# Sheet_1_2020-09-11_10-02-54.net
KiCad netlist of a schematic drawn in Altium Designer
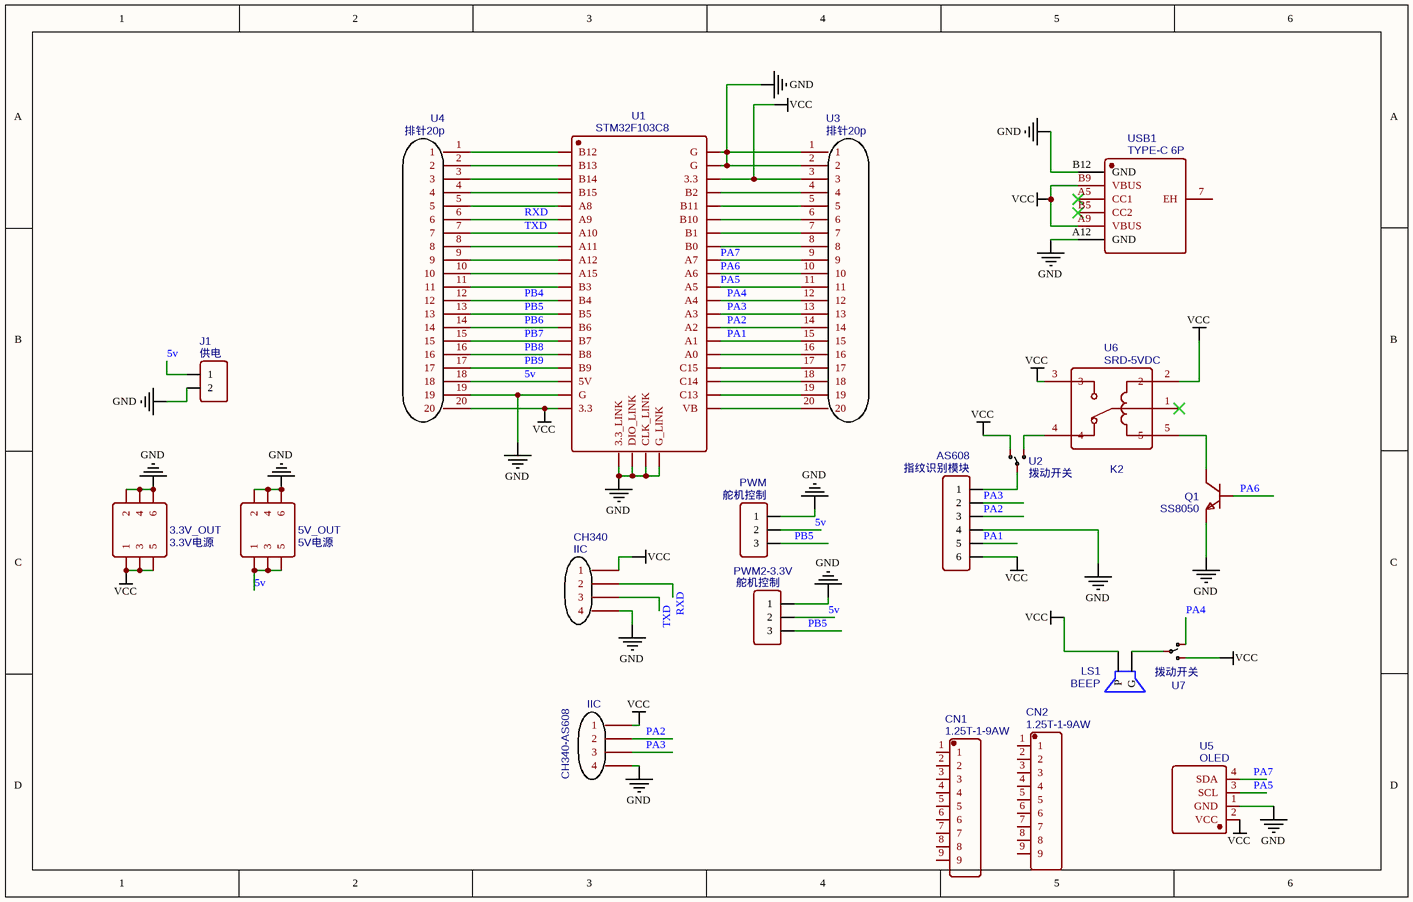
[diagram p0: Sheet_1_2020-09-11_10-02-54.schdoc]

(export (version "E")
  (design (tool "Eeschema 10.0.6"))
  (components
    (comp (ref "3.3V_OUT")
      (value "3.3V电源")
      (footprint "HDR-TH_6P-P2.54-V-R2-C3-S2.54")
      (fields
        (field (name "BOM_MANUFACTURER PART") "Header-Male-2.54_2x3")
        (field (name "BOM_SUPPLIER PART") "C65114")
      )
      (libsource (lib "altium-import") (part "root_1_3.3V电源_"))
    )
    (comp (ref "5V_OUT")
      (value "5V电源")
      (footprint "HDR-TH_6P-P2.54-V-R2-C3-S2.54")
      (fields
        (field (name "BOM_MANUFACTURER PART") "Header-Male-2.54_2x3")
        (field (name "BOM_SUPPLIER PART") "C65114")
      )
      (libsource (lib "altium-import") (part "root_1_5V电源_"))
    )
    (comp (ref "AS608")
      (value "指纹识别模块")
      (footprint "HDR-M-2.54_1X6")
      (fields (field (name "BOM_SUPPLIER PART") "C190819") (field (name "CONTRIBUTOR") "LCEDA_Lib"))
      (libsource (lib "altium-import") (part "root_0_指纹识别模块_"))
    )
    (comp (ref "CH340")
      (value "IIC")
      (footprint "HANDER*4")
      (fields (field (name "CONTRIBUTOR") "lzzzzzz"))
      (libsource (lib "altium-import") (part "root_0_IIC_"))
    )
    (comp (ref "CH340-AS608")
      (value "IIC")
      (footprint "HANDER*4")
      (fields (field (name "CONTRIBUTOR") "lzzzzzz"))
      (libsource (lib "altium-import") (part "root_0_IIC_"))
    )
    (comp (ref "CN1")
      (value "1.25T-1-9AW")
      (footprint "CONN-TH_9P-P1.25-H_1.25T-1-9AW")
      (fields (field (name "BOM_SUPPLIER PART") "C10839"))
      (libsource (lib "altium-import") (part "root_0_1.25T-1-9AW_"))
    )
    (comp (ref "CN2")
      (value "1.25T-1-9AW")
      (footprint "CONN-TH_9P-P1.25-H_1.25T-1-9AW")
      (fields (field (name "BOM_SUPPLIER PART") "C10839"))
      (libsource (lib "altium-import") (part "root_0_1.25T-1-9AW_"))
    )
    (comp (ref "J1")
      (value "供电")
      (footprint "HDR-M-2.54_1X2")
      (fields (field (name "BOM_SUPPLIER PART") "C124375") (field (name "CONTRIBUTOR") "LCEDA_Lib"))
      (libsource (lib "altium-import") (part "root_0_供电_"))
    )
    (comp (ref "LS1")
      (value "BEEP")
      (footprint "BEEP-9")
      (fields (field (name "CONTRIBUTOR") "nibo"))
      (libsource (lib "altium-import") (part "root_3_BEEP_"))
    )
    (comp (ref "PWM")
      (value "舵机控制")
      (footprint "HDR-M-2.54_1X3")
      (fields (field (name "BOM_SUPPLIER PART") "C180248") (field (name "CONTRIBUTOR") "LCEDA_Lib"))
      (libsource (lib "altium-import") (part "root_0_舵机控制_"))
    )
    (comp (ref "PWM2-3.3V")
      (value "舵机控制")
      (footprint "HDR-M-2.54_1X3")
      (fields (field (name "BOM_SUPPLIER PART") "C180248") (field (name "CONTRIBUTOR") "LCEDA_Lib"))
      (libsource (lib "altium-import") (part "root_0_舵机控制_"))
    )
    (comp (ref "Q1")
      (value "SS8050")
      (footprint "TO-92_FORMING1")
      (fields (field (name "BOM_SUPPLIER PART") "C80297"))
      (libsource (lib "altium-import") (part "root_0_SS8050_"))
    )
    (comp (ref "U1")
      (value "STM32F103C8")
      (footprint "STM32F103C8T6-CORE")
      (fields (field (name "CONTRIBUTOR") "TMHZ"))
      (libsource (lib "altium-import") (part "root_0_STM32F103C8_"))
    )
    (comp (ref "U2")
      (value "拨动开关")
      (footprint "拨动开关-SS12D00G3")
      (fields (field (name "CONTRIBUTOR") "ShiKerFamily"))
      (libsource (lib "altium-import") (part "root_2_拨动开关_"))
    )
    (comp (ref "U3")
      (value "排针20p")
      (footprint "排针-2.54间距-1*20P")
      (fields (field (name "CONTRIBUTOR") "liugj"))
      (libsource (lib "") (part "root_0_排针20p__1"))
    )
    (comp (ref "U4")
      (value "排针20p")
      (footprint "排针-2.54间距-1*20P")
      (fields (field (name "CONTRIBUTOR") "liugj"))
      (libsource (lib "altium-import") (part "root_0_排针20p_"))
    )
    (comp (ref "U5")
      (value "OLED")
      (footprint "0.96_OLED")
      (fields (field (name "CONTRIBUTOR") "Sheikah"))
      (libsource (lib "altium-import") (part "root_2_OLED_"))
    )
    (comp (ref "U6")
      (value "SRD-5VDC")
      (footprint "SRD-05VDC-SL-C")
      (fields (field (name "CONTRIBUTOR") "Jensen"))
      (libsource (lib "altium-import") (part "root_2_SRD-5VDC_"))
    )
    (comp (ref "U7")
      (value "拨动开关")
      (footprint "拨动开关-SS12D00G3")
      (fields (field (name "CONTRIBUTOR") "ShiKerFamily"))
      (libsource (lib "altium-import") (part "root_1_拨动开关_"))
    )
    (comp (ref "USB1")
      (value "TYPE-C 6P")
      (footprint "TYPE-C-SMD_TYPE-C-6P")
      (fields (field (name "BOM_SUPPLIER PART") "C456012") (field (name "CONTRIBUTOR") "youzige"))
      (libsource (lib "altium-import") (part "root_0_TYPE-C 6P_"))
    )
  )
  (nets
    (net (code "1") (name "/5v") (class "Default")
      (node (ref "5V_OUT") (pin "1") (pinfunction "1_1") (pintype "passive"))
      (node (ref "5V_OUT") (pin "3") (pinfunction "3_3") (pintype "passive"))
      (node (ref "5V_OUT") (pin "5") (pinfunction "5_5") (pintype "passive"))
      (node (ref "J1") (pin "1") (pinfunction "1_1") (pintype "passive"))
      (node (ref "PWM") (pin "2") (pinfunction "2_2") (pintype "passive"))
      (node (ref "PWM2-3.3V") (pin "2") (pinfunction "2_2") (pintype "passive"))
      (node (ref "U1") (pin "18") (pinfunction "5V_18") (pintype "passive"))
      (node (ref "U4") (pin "18") (pinfunction "18_18") (pintype "passive"))
    )
    (net (code "2") (name "/PA1") (class "Default")
      (node (ref "AS608") (pin "5") (pinfunction "5_5") (pintype "passive"))
      (node (ref "U1") (pin "26") (pinfunction "A1_26") (pintype "passive"))
      (node (ref "U3") (pin "15") (pinfunction "15_15") (pintype "passive"))
    )
    (net (code "3") (name "/PA2") (class "Default")
      (node (ref "AS608") (pin "3") (pinfunction "3_3") (pintype "passive"))
      (node (ref "CH340-AS608") (pin "2") (pinfunction "2_2") (pintype "passive"))
      (node (ref "U1") (pin "27") (pinfunction "A2_27") (pintype "passive"))
      (node (ref "U3") (pin "14") (pinfunction "14_14") (pintype "passive"))
    )
    (net (code "4") (name "/PA3") (class "Default")
      (node (ref "AS608") (pin "2") (pinfunction "2_2") (pintype "passive"))
      (node (ref "CH340-AS608") (pin "3") (pinfunction "3_3") (pintype "passive"))
      (node (ref "U1") (pin "28") (pinfunction "A3_28") (pintype "passive"))
      (node (ref "U3") (pin "13") (pinfunction "13_13") (pintype "passive"))
    )
    (net (code "5") (name "/PA4") (class "Default")
      (node (ref "U1") (pin "29") (pinfunction "A4_29") (pintype "passive"))
      (node (ref "U3") (pin "12") (pinfunction "12_12") (pintype "passive"))
      (node (ref "U7") (pin "3") (pinfunction "3_3") (pintype "passive"))
    )
    (net (code "6") (name "/PA5") (class "Default")
      (node (ref "U1") (pin "30") (pinfunction "A5_30") (pintype "passive"))
      (node (ref "U3") (pin "11") (pinfunction "11_11") (pintype "passive"))
      (node (ref "U5") (pin "3") (pinfunction "SCL_3") (pintype "passive"))
    )
    (net (code "7") (name "/PA6") (class "Default")
      (node (ref "Q1") (pin "2") (pinfunction "B_2") (pintype "passive"))
      (node (ref "U1") (pin "31") (pinfunction "A6_31") (pintype "passive"))
      (node (ref "U3") (pin "10") (pinfunction "10_10") (pintype "passive"))
    )
    (net (code "8") (name "/PA7") (class "Default")
      (node (ref "U1") (pin "32") (pinfunction "A7_32") (pintype "passive"))
      (node (ref "U3") (pin "9") (pinfunction "9_9") (pintype "passive"))
      (node (ref "U5") (pin "4") (pinfunction "SDA_4") (pintype "passive"))
    )
    (net (code "9") (name "/PB4") (class "Default")
      (node (ref "U1") (pin "12") (pinfunction "B4_12") (pintype "passive"))
      (node (ref "U4") (pin "12") (pinfunction "12_12") (pintype "passive"))
    )
    (net (code "10") (name "/PB5") (class "Default")
      (node (ref "PWM") (pin "3") (pinfunction "3_3") (pintype "passive"))
      (node (ref "PWM2-3.3V") (pin "3") (pinfunction "3_3") (pintype "passive"))
      (node (ref "U1") (pin "13") (pinfunction "B5_13") (pintype "passive"))
      (node (ref "U4") (pin "13") (pinfunction "13_13") (pintype "passive"))
    )
    (net (code "11") (name "/PB6") (class "Default")
      (node (ref "U1") (pin "14") (pinfunction "B6_14") (pintype "passive"))
      (node (ref "U4") (pin "14") (pinfunction "14_14") (pintype "passive"))
    )
    (net (code "12") (name "/PB7") (class "Default")
      (node (ref "U1") (pin "15") (pinfunction "B7_15") (pintype "passive"))
      (node (ref "U4") (pin "15") (pinfunction "15_15") (pintype "passive"))
    )
    (net (code "13") (name "/PB8") (class "Default")
      (node (ref "U1") (pin "16") (pinfunction "B8_16") (pintype "passive"))
      (node (ref "U4") (pin "16") (pinfunction "16_16") (pintype "passive"))
    )
    (net (code "14") (name "/PB9") (class "Default")
      (node (ref "U1") (pin "17") (pinfunction "B9_17") (pintype "passive"))
      (node (ref "U4") (pin "17") (pinfunction "17_17") (pintype "passive"))
    )
    (net (code "15") (name "/RXD") (class "Default")
      (node (ref "CH340") (pin "2") (pinfunction "2_2") (pintype "passive"))
      (node (ref "U1") (pin "6") (pinfunction "A9_6") (pintype "passive"))
      (node (ref "U4") (pin "6") (pinfunction "6_6") (pintype "passive"))
    )
    (net (code "16") (name "/TXD") (class "Default")
      (node (ref "CH340") (pin "3") (pinfunction "3_3") (pintype "passive"))
      (node (ref "U1") (pin "7") (pinfunction "A10_7") (pintype "passive"))
      (node (ref "U4") (pin "7") (pinfunction "7_7") (pintype "passive"))
    )
    (net (code "17") (name "GND") (class "Default")
      (node (ref "3.3V_OUT") (pin "2") (pinfunction "2_2") (pintype "passive"))
      (node (ref "3.3V_OUT") (pin "4") (pinfunction "4_4") (pintype "passive"))
      (node (ref "3.3V_OUT") (pin "6") (pinfunction "6_6") (pintype "passive"))
      (node (ref "5V_OUT") (pin "2") (pinfunction "2_2") (pintype "passive"))
      (node (ref "5V_OUT") (pin "4") (pinfunction "4_4") (pintype "passive"))
      (node (ref "5V_OUT") (pin "6") (pinfunction "6_6") (pintype "passive"))
      (node (ref "AS608") (pin "4") (pinfunction "4_4") (pintype "passive"))
      (node (ref "CH340") (pin "4") (pinfunction "4_4") (pintype "passive"))
      (node (ref "CH340-AS608") (pin "4") (pinfunction "4_4") (pintype "passive"))
      (node (ref "J1") (pin "2") (pinfunction "2_2") (pintype "passive"))
      (node (ref "PWM") (pin "1") (pinfunction "1_1") (pintype "passive"))
      (node (ref "PWM2-3.3V") (pin "1") (pinfunction "1_1") (pintype "passive"))
      (node (ref "Q1") (pin "1") (pinfunction "E_1") (pintype "passive"))
      (node (ref "U1") (pin "19") (pinfunction "G_19") (pintype "passive"))
      (node (ref "U1") (pin "39") (pinfunction "G_39") (pintype "passive"))
      (node (ref "U1") (pin "40") (pinfunction "G_40") (pintype "passive"))
      (node (ref "U1") (pin "41") (pinfunction "3.3_LINK_41") (pintype "passive"))
      (node (ref "U1") (pin "42") (pinfunction "DIO_LINK_42") (pintype "passive"))
      (node (ref "U1") (pin "43") (pinfunction "CLK_LINK_43") (pintype "passive"))
      (node (ref "U1") (pin "44") (pinfunction "G_LINK_44") (pintype "passive"))
      (node (ref "U3") (pin "1") (pinfunction "1_1") (pintype "passive"))
      (node (ref "U3") (pin "2") (pinfunction "2_2") (pintype "passive"))
      (node (ref "U4") (pin "19") (pinfunction "19_19") (pintype "passive"))
      (node (ref "U5") (pin "1") (pinfunction "GND_1") (pintype "passive"))
      (node (ref "USB1") (pin "A12") (pinfunction "GND_A12") (pintype "passive"))
      (node (ref "USB1") (pin "B12") (pinfunction "GND_B12") (pintype "passive"))
    )
    (net (code "18") (name "Net-(AS608-Pad1)") (class "Default")
      (node (ref "AS608") (pin "1") (pinfunction "1_1") (pintype "passive"))
      (node (ref "U2") (pin "2") (pinfunction "2_2") (pintype "passive"))
    )
    (net (code "19") (name "Net-(LS1-G)") (class "Default")
      (node (ref "LS1") (pin "2") (pinfunction "G_2") (pintype "passive"))
      (node (ref "U7") (pin "2") (pinfunction "2_2") (pintype "passive"))
    )
    (net (code "20") (name "Net-(Q1-C)") (class "Default")
      (node (ref "Q1") (pin "3") (pinfunction "C_3") (pintype "passive"))
      (node (ref "U6") (pin "5") (pinfunction "5_5") (pintype "passive"))
    )
    (net (code "21") (name "Net-(U1-A0)") (class "Default")
      (node (ref "U1") (pin "25") (pinfunction "A0_25") (pintype "passive"))
      (node (ref "U3") (pin "16") (pinfunction "16_16") (pintype "passive"))
    )
    (net (code "22") (name "Net-(U1-A8)") (class "Default")
      (node (ref "U1") (pin "5") (pinfunction "A8_5") (pintype "passive"))
      (node (ref "U4") (pin "5") (pinfunction "5_5") (pintype "passive"))
    )
    (net (code "23") (name "Net-(U1-A11)") (class "Default")
      (node (ref "U1") (pin "8") (pinfunction "A11_8") (pintype "passive"))
      (node (ref "U4") (pin "8") (pinfunction "8_8") (pintype "passive"))
    )
    (net (code "24") (name "Net-(U1-A12)") (class "Default")
      (node (ref "U1") (pin "9") (pinfunction "A12_9") (pintype "passive"))
      (node (ref "U4") (pin "9") (pinfunction "9_9") (pintype "passive"))
    )
    (net (code "25") (name "Net-(U1-A15)") (class "Default")
      (node (ref "U1") (pin "10") (pinfunction "A15_10") (pintype "passive"))
      (node (ref "U4") (pin "10") (pinfunction "10_10") (pintype "passive"))
    )
    (net (code "26") (name "Net-(U1-B0)") (class "Default")
      (node (ref "U1") (pin "33") (pinfunction "B0_33") (pintype "passive"))
      (node (ref "U3") (pin "8") (pinfunction "8_8") (pintype "passive"))
    )
    (net (code "27") (name "Net-(U1-B1)") (class "Default")
      (node (ref "U1") (pin "34") (pinfunction "B1_34") (pintype "passive"))
      (node (ref "U3") (pin "7") (pinfunction "7_7") (pintype "passive"))
    )
    (net (code "28") (name "Net-(U1-B2)") (class "Default")
      (node (ref "U1") (pin "37") (pinfunction "B2_37") (pintype "passive"))
      (node (ref "U3") (pin "4") (pinfunction "4_4") (pintype "passive"))
    )
    (net (code "29") (name "Net-(U1-B3)") (class "Default")
      (node (ref "U1") (pin "11") (pinfunction "B3_11") (pintype "passive"))
      (node (ref "U4") (pin "11") (pinfunction "11_11") (pintype "passive"))
    )
    (net (code "30") (name "Net-(U1-B10)") (class "Default")
      (node (ref "U1") (pin "35") (pinfunction "B10_35") (pintype "passive"))
      (node (ref "U3") (pin "6") (pinfunction "6_6") (pintype "passive"))
    )
    (net (code "31") (name "Net-(U1-B11)") (class "Default")
      (node (ref "U1") (pin "36") (pinfunction "B11_36") (pintype "passive"))
      (node (ref "U3") (pin "5") (pinfunction "5_5") (pintype "passive"))
    )
    (net (code "32") (name "Net-(U1-B12)") (class "Default")
      (node (ref "U1") (pin "1") (pinfunction "B12_1") (pintype "passive"))
      (node (ref "U4") (pin "1") (pinfunction "1_1") (pintype "passive"))
    )
    (net (code "33") (name "Net-(U1-B13)") (class "Default")
      (node (ref "U1") (pin "2") (pinfunction "B13_2") (pintype "passive"))
      (node (ref "U4") (pin "2") (pinfunction "2_2") (pintype "passive"))
    )
    (net (code "34") (name "Net-(U1-B14)") (class "Default")
      (node (ref "U1") (pin "3") (pinfunction "B14_3") (pintype "passive"))
      (node (ref "U4") (pin "3") (pinfunction "3_3") (pintype "passive"))
    )
    (net (code "35") (name "Net-(U1-B15)") (class "Default")
      (node (ref "U1") (pin "4") (pinfunction "B15_4") (pintype "passive"))
      (node (ref "U4") (pin "4") (pinfunction "4_4") (pintype "passive"))
    )
    (net (code "36") (name "Net-(U1-C13)") (class "Default")
      (node (ref "U1") (pin "22") (pinfunction "C13_22") (pintype "passive"))
      (node (ref "U3") (pin "19") (pinfunction "19_19") (pintype "passive"))
    )
    (net (code "37") (name "Net-(U1-C14)") (class "Default")
      (node (ref "U1") (pin "23") (pinfunction "C14_23") (pintype "passive"))
      (node (ref "U3") (pin "18") (pinfunction "18_18") (pintype "passive"))
    )
    (net (code "38") (name "Net-(U1-C15)") (class "Default")
      (node (ref "U1") (pin "24") (pinfunction "C15_24") (pintype "passive"))
      (node (ref "U3") (pin "17") (pinfunction "17_17") (pintype "passive"))
    )
    (net (code "39") (name "Net-(U1-VB)") (class "Default")
      (node (ref "U1") (pin "21") (pinfunction "VB_21") (pintype "passive"))
      (node (ref "U3") (pin "20") (pinfunction "20_20") (pintype "passive"))
    )
    (net (code "40") (name "Net-(U2-Pad1)") (class "Default")
      (node (ref "U2") (pin "1") (pinfunction "1_1") (pintype "passive"))
      (node (ref "U6") (pin "4") (pinfunction "4_4") (pintype "passive"))
    )
    (net (code "41") (name "VCC") (class "Default")
      (node (ref "3.3V_OUT") (pin "1") (pinfunction "1_1") (pintype "passive"))
      (node (ref "3.3V_OUT") (pin "3") (pinfunction "3_3") (pintype "passive"))
      (node (ref "3.3V_OUT") (pin "5") (pinfunction "5_5") (pintype "passive"))
      (node (ref "AS608") (pin "6") (pinfunction "6_6") (pintype "passive"))
      (node (ref "CH340") (pin "1") (pinfunction "1_1") (pintype "passive"))
      (node (ref "CH340-AS608") (pin "1") (pinfunction "1_1") (pintype "passive"))
      (node (ref "LS1") (pin "1") (pinfunction "P_1") (pintype "passive"))
      (node (ref "U1") (pin "20") (pinfunction "3.3_20") (pintype "passive"))
      (node (ref "U1") (pin "38") (pinfunction "3.3_38") (pintype "passive"))
      (node (ref "U2") (pin "3") (pinfunction "3_3") (pintype "passive"))
      (node (ref "U3") (pin "3") (pinfunction "3_3") (pintype "passive"))
      (node (ref "U4") (pin "20") (pinfunction "20_20") (pintype "passive"))
      (node (ref "U5") (pin "2") (pinfunction "VCC_2") (pintype "passive"))
      (node (ref "U6") (pin "2") (pinfunction "2_2") (pintype "passive"))
      (node (ref "U6") (pin "3") (pinfunction "3_3") (pintype "passive"))
      (node (ref "U7") (pin "1") (pinfunction "1_1") (pintype "passive"))
      (node (ref "USB1") (pin "A9") (pinfunction "VBUS_A9") (pintype "passive"))
      (node (ref "USB1") (pin "B9") (pinfunction "VBUS_B9") (pintype "passive"))
    )
    (net (code "42") (name "unconnected-(CN1-Pad1)") (class "Default")
      (node (ref "CN1") (pin "1") (pinfunction "1_1") (pintype "passive"))
    )
    (net (code "43") (name "unconnected-(CN1-Pad2)") (class "Default")
      (node (ref "CN1") (pin "2") (pinfunction "2_2") (pintype "passive"))
    )
    (net (code "44") (name "unconnected-(CN1-Pad3)") (class "Default")
      (node (ref "CN1") (pin "3") (pinfunction "3_3") (pintype "passive"))
    )
    (net (code "45") (name "unconnected-(CN1-Pad4)") (class "Default")
      (node (ref "CN1") (pin "4") (pinfunction "4_4") (pintype "passive"))
    )
    (net (code "46") (name "unconnected-(CN1-Pad5)") (class "Default")
      (node (ref "CN1") (pin "5") (pinfunction "5_5") (pintype "passive"))
    )
    (net (code "47") (name "unconnected-(CN1-Pad6)") (class "Default")
      (node (ref "CN1") (pin "6") (pinfunction "6_6") (pintype "passive"))
    )
    (net (code "48") (name "unconnected-(CN1-Pad7)") (class "Default")
      (node (ref "CN1") (pin "7") (pinfunction "7_7") (pintype "passive"))
    )
    (net (code "49") (name "unconnected-(CN1-Pad8)") (class "Default")
      (node (ref "CN1") (pin "8") (pinfunction "8_8") (pintype "passive"))
    )
    (net (code "50") (name "unconnected-(CN1-Pad9)") (class "Default")
      (node (ref "CN1") (pin "9") (pinfunction "9_9") (pintype "passive"))
    )
    (net (code "51") (name "unconnected-(CN2-Pad1)") (class "Default")
      (node (ref "CN2") (pin "1") (pinfunction "1_1") (pintype "passive"))
    )
    (net (code "52") (name "unconnected-(CN2-Pad2)") (class "Default")
      (node (ref "CN2") (pin "2") (pinfunction "2_2") (pintype "passive"))
    )
    (net (code "53") (name "unconnected-(CN2-Pad3)") (class "Default")
      (node (ref "CN2") (pin "3") (pinfunction "3_3") (pintype "passive"))
    )
    (net (code "54") (name "unconnected-(CN2-Pad4)") (class "Default")
      (node (ref "CN2") (pin "4") (pinfunction "4_4") (pintype "passive"))
    )
    (net (code "55") (name "unconnected-(CN2-Pad5)") (class "Default")
      (node (ref "CN2") (pin "5") (pinfunction "5_5") (pintype "passive"))
    )
    (net (code "56") (name "unconnected-(CN2-Pad6)") (class "Default")
      (node (ref "CN2") (pin "6") (pinfunction "6_6") (pintype "passive"))
    )
    (net (code "57") (name "unconnected-(CN2-Pad7)") (class "Default")
      (node (ref "CN2") (pin "7") (pinfunction "7_7") (pintype "passive"))
    )
    (net (code "58") (name "unconnected-(CN2-Pad8)") (class "Default")
      (node (ref "CN2") (pin "8") (pinfunction "8_8") (pintype "passive"))
    )
    (net (code "59") (name "unconnected-(CN2-Pad9)") (class "Default")
      (node (ref "CN2") (pin "9") (pinfunction "9_9") (pintype "passive"))
    )
    (net (code "60") (name "unconnected-(U6-Pad1)") (class "Default")
      (node (ref "U6") (pin "1") (pinfunction "1_1") (pintype "passive+no_connect"))
    )
    (net (code "61") (name "unconnected-(USB1-CC1-PadA5)") (class "Default")
      (node (ref "USB1") (pin "A5") (pinfunction "CC1_A5") (pintype "passive+no_connect"))
    )
    (net (code "62") (name "unconnected-(USB1-CC2-PadB5)") (class "Default")
      (node (ref "USB1") (pin "B5") (pinfunction "CC2_B5") (pintype "passive+no_connect"))
    )
    (net (code "63") (name "unconnected-(USB1-EH-Pad7)") (class "Default")
      (node (ref "USB1") (pin "7") (pinfunction "EH_7") (pintype "passive"))
    )
  )
)
